# Power.net
KiCad netlist of a schematic drawn in Altium Designer
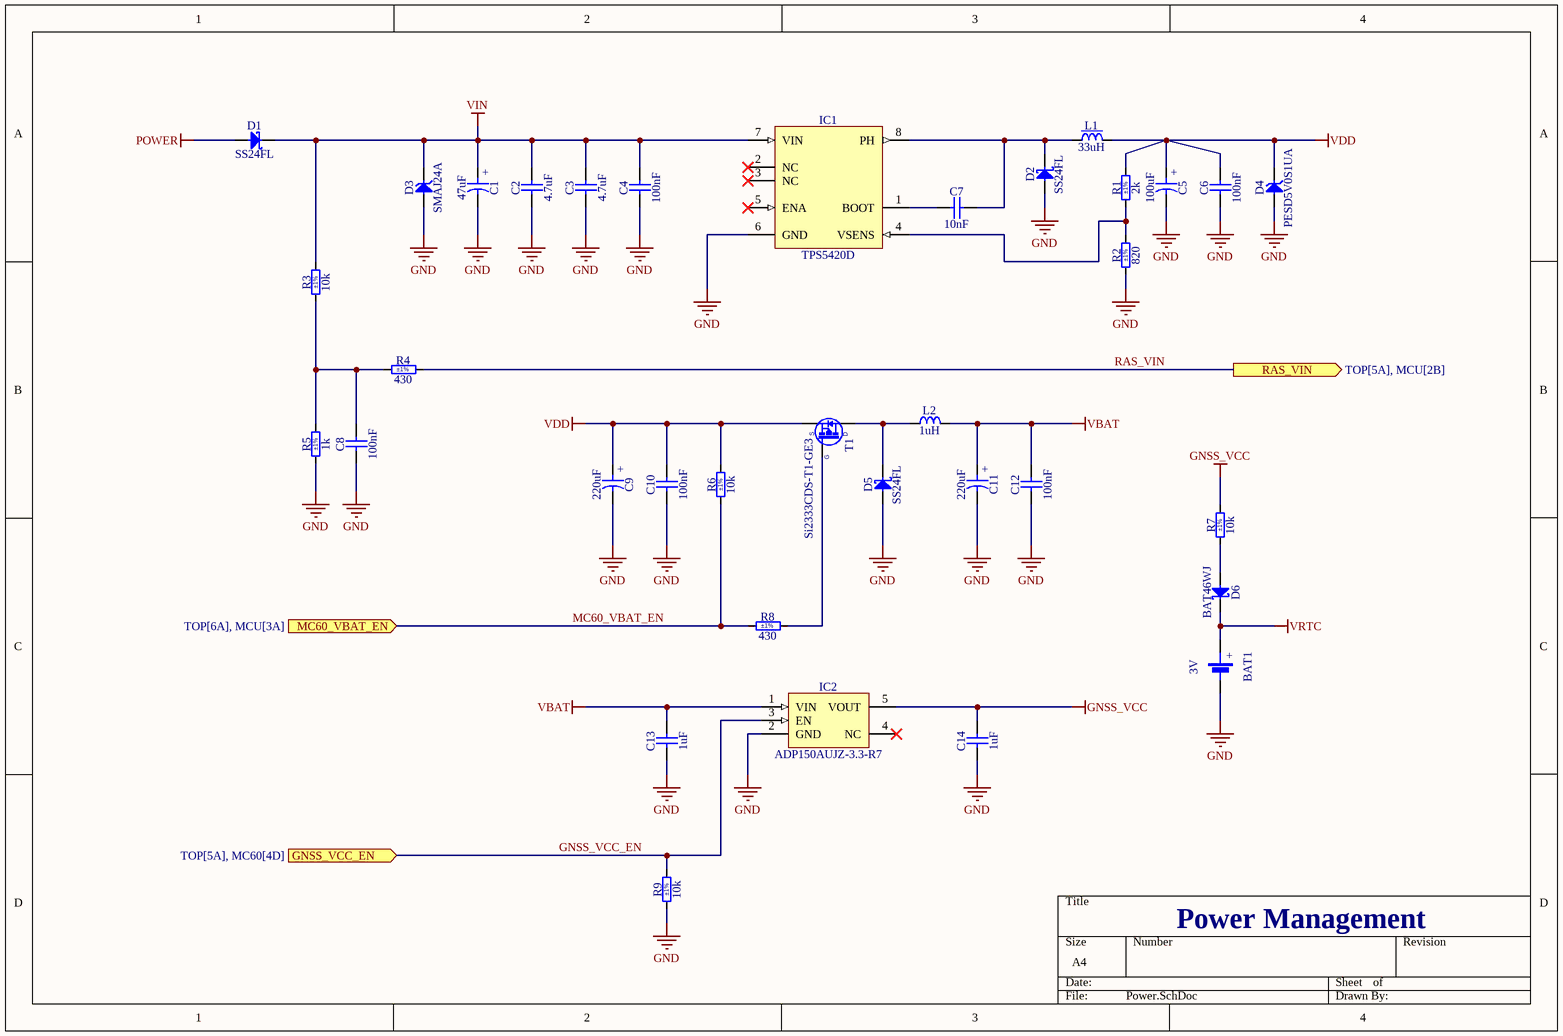
[diagram p0: Power.SchDoc]

(export (version "E")
  (design (tool "Eeschema 10.0.6"))
  (components
    (comp (ref "BAT1")
      (value "3V")
      (footprint "BAT_SEIKO_ML414H_IV01E")
      (description "Battery 2 Pin")
      (fields
        (field (name "PART NUMBER") "BAT_SEIKO_ML414H_IV01E")
        (field (name "POWER") "1mAh")
        (field (name "AUTHOR") "Xusniyor")
      )
      (libsource (lib "Eletro-mechanical") (part "Battery 2 Pin"))
    )
    (comp (ref "C1")
      (value "47uF")
      (footprint "CAPAE660X540N")
      (description "Polarised capacitor")
      (fields
        (field (name "PART NUMBER") "CAE660-540_47UF_35V_20%")
        (field (name "VOLTAGE") "35V")
        (field (name "AUTHOR") "CERN DEM JLC")
      )
      (libsource (lib "Capacitors") (part "Capacitor - polarized"))
    )
    (comp (ref "C2")
      (value "4.7uF")
      (footprint "CAPC5750X200N")
      (description "Non-polarised capacitor")
      (fields
        (field (name "PART NUMBER") "CC2220_4.7UF_100V_10%_X7R")
        (field (name "VOLTAGE") "100V")
        (field (name "AUTHOR") "CERN DEM JLC")
      )
      (libsource (lib "Capacitors") (part "Capacitor - non polarized"))
    )
    (comp (ref "C3")
      (value "4.7uF")
      (footprint "CAPC5750X200N")
      (description "Non-polarised capacitor")
      (fields
        (field (name "PART NUMBER") "CC2220_4.7UF_100V_10%_X7R")
        (field (name "VOLTAGE") "100V")
        (field (name "AUTHOR") "CERN DEM JLC")
      )
      (libsource (lib "Capacitors") (part "Capacitor - non polarized"))
    )
    (comp (ref "C4")
      (value "100nF")
      (footprint "CAPC1608X90N")
      (description "Non-polarised capacitor")
      (fields
        (field (name "PART NUMBER") "CC0603_100NF_100V_10%_X7R")
        (field (name "VOLTAGE") "100V")
        (field (name "AUTHOR") "CERN DEM JLC")
      )
      (libsource (lib "Capacitors") (part "Capacitor - non polarized"))
    )
    (comp (ref "C5")
      (value "100uF")
      (footprint "CAPMP7343X310N")
      (description "Polarised capacitor")
      (fields
        (field (name "PART NUMBER") "CTE7343-31_100UF_10V_10%_LESR0050")
        (field (name "VOLTAGE") "10V")
        (field (name "AUTHOR") "CERN DEM JLC")
      )
      (libsource (lib "Capacitors") (part "Capacitor - polarized"))
    )
    (comp (ref "C6")
      (value "100nF")
      (footprint "CAPC1608X87N")
      (description "Non-polarised capacitor")
      (fields
        (field (name "PART NUMBER") "CC0603_100NF_50V_10%_X7R")
        (field (name "VOLTAGE") "50V")
        (field (name "AUTHOR") "CERN DEM JLC")
      )
      (libsource (lib "Capacitors") (part "Capacitor - non polarized"))
    )
    (comp (ref "C7")
      (value "10nF")
      (footprint "CAPC1608X87N")
      (description "Non-polarised capacitor")
      (fields
        (field (name "PART NUMBER") "CC0603_10NF_50V_10%_X7R")
        (field (name "VOLTAGE") "50V")
        (field (name "AUTHOR") "CERN DEM JLC")
      )
      (libsource (lib "Capacitors") (part "Capacitor - non polarized"))
    )
    (comp (ref "C8")
      (value "100nF")
      (footprint "CAPC1608X87N")
      (description "Non-polarised capacitor")
      (fields
        (field (name "PART NUMBER") "CC0603_100NF_50V_10%_X7R")
        (field (name "VOLTAGE") "50V")
        (field (name "AUTHOR") "CERN DEM JLC")
      )
      (libsource (lib "Capacitors") (part "Capacitor - non polarized"))
    )
    (comp (ref "C9")
      (value "220uF")
      (footprint "CAPAE830X620N")
      (description "Polarised capacitor")
      (fields
        (field (name "PART NUMBER") "CAE830-620_220UF_10V_20%")
        (field (name "VOLTAGE") "10V")
        (field (name "AUTHOR") "CERN DEM JLC")
      )
      (libsource (lib "Capacitors") (part "Capacitor - polarized"))
    )
    (comp (ref "C10")
      (value "100nF")
      (footprint "CAPC1608X87N")
      (description "Non-polarised capacitor")
      (fields
        (field (name "PART NUMBER") "CC0603_100NF_50V_10%_X7R")
        (field (name "VOLTAGE") "50V")
        (field (name "AUTHOR") "CERN DEM JLC")
      )
      (libsource (lib "Capacitors") (part "Capacitor - non polarized"))
    )
    (comp (ref "C11")
      (value "220uF")
      (footprint "CAPAE830X620N")
      (description "Polarised capacitor")
      (fields
        (field (name "PART NUMBER") "CAE830-620_220UF_10V_20%")
        (field (name "VOLTAGE") "10V")
        (field (name "AUTHOR") "CERN DEM JLC")
      )
      (libsource (lib "Capacitors") (part "Capacitor - polarized"))
    )
    (comp (ref "C12")
      (value "100nF")
      (footprint "CAPC1608X87N")
      (description "Non-polarised capacitor")
      (fields
        (field (name "PART NUMBER") "CC0603_100NF_50V_10%_X7R")
        (field (name "VOLTAGE") "50V")
        (field (name "AUTHOR") "CERN DEM JLC")
      )
      (libsource (lib "Capacitors") (part "Capacitor - non polarized"))
    )
    (comp (ref "C13")
      (value "1uF")
      (footprint "CAPC1608X90N")
      (description "Non-polarised capacitor")
      (fields
        (field (name "PART NUMBER") "CC0603_1UF_50V_10%_X7R")
        (field (name "VOLTAGE") "50V")
        (field (name "AUTHOR") "CERN DEM BC")
      )
      (libsource (lib "Capacitors") (part "Capacitor - non polarized"))
    )
    (comp (ref "C14")
      (value "1uF")
      (footprint "CAPC1608X90N")
      (description "Non-polarised capacitor")
      (fields
        (field (name "PART NUMBER") "CC0603_1UF_50V_10%_X7R")
        (field (name "VOLTAGE") "50V")
        (field (name "AUTHOR") "CERN DEM BC")
      )
      (libsource (lib "Capacitors") (part "Capacitor - non polarized"))
    )
    (comp (ref "D1")
      (value "SS24FL")
      (footprint "SODFL3617X108N")
      (description "Schottky Diode")
      (fields
        (field (name "VOLTAGE") "40V")
        (field (name "POWER") "2A")
        (field (name "AUTHOR") "CERN DEM BC")
      )
      (libsource (lib "ICs And Semiconductors") (part "Diode Schottky"))
    )
    (comp (ref "D2")
      (value "SS24FL")
      (footprint "SODFL3617X108N")
      (description "Schottky Diode")
      (fields
        (field (name "VOLTAGE") "40V")
        (field (name "POWER") "2A")
        (field (name "AUTHOR") "CERN DEM BC")
      )
      (libsource (lib "ICs And Semiconductors") (part "Diode Schottky"))
    )
    (comp (ref "D3")
      (value "SMAJ24A")
      (footprint "DIOM5226X262N")
      (description "Transient Voltage Suppressor Diode (Uni-Directional)")
      (fields
        (field (name "VOLTAGE") "24V")
        (field (name "POWER") "400W")
        (field (name "AUTHOR") "CERN DEM JLC")
      )
      (libsource (lib "ICs And Semiconductors") (part "Diode TVS Uni-Directional"))
    )
    (comp (ref "D4")
      (value "PESD5V0S1UA")
      (footprint "SOD2512X110N")
      (description "Transient Voltage Suppressor Diode (Uni-Directional)")
      (fields
        (field (name "VOLTAGE") "5V")
        (field (name "POWER") "890W")
        (field (name "AUTHOR") "CERN DEM JLC")
      )
      (libsource (lib "ICs And Semiconductors") (part "Diode TVS Uni-Directional"))
    )
    (comp (ref "D5")
      (value "SS24FL")
      (footprint "SODFL3617X108N")
      (description "Schottky Diode")
      (fields
        (field (name "VOLTAGE") "40V")
        (field (name "POWER") "2A")
        (field (name "AUTHOR") "CERN DEM BC")
      )
      (libsource (lib "ICs And Semiconductors") (part "Diode Schottky"))
    )
    (comp (ref "D6")
      (value "BAT46WJ")
      (footprint "SODFL2513X80N")
      (description "Schottky Diode")
      (fields
        (field (name "VOLTAGE") "100V")
        (field (name "POWER") "250mA")
        (field (name "AUTHOR") "CERN DEM JLC")
      )
      (libsource (lib "ICs And Semiconductors") (part "Diode Schottky"))
    )
    (comp (ref "IC1")
      (value "TPS5420D")
      (footprint "SOIC127P600X175-8N")
      (description "2A, Wide Input Range, Step-Down SWIFT Converter")
      (fields (field (name "MANUFACTURER") "TEXAS INSTRUMENTS") (field (name "AUTHOR") "CERN DEM JLC"))
      (libsource (lib "ICs And Semiconductors") (part "TPS5420"))
    )
    (comp (ref "IC2")
      (value "ADP150AUJZ-3.3-R7")
      (footprint "SOT95P280X90-5N")
      (description "Ultralow Noise, 150 mA CMOS Linear Regulator")
      (fields (field (name "MANUFACTURER") "ANALOG DEVICES") (field (name "AUTHOR") "CERN DEM JLC"))
      (libsource (lib "ICs And Semiconductors") (part "ADP150AUJZ"))
    )
    (comp (ref "L1")
      (value "33uH")
      (footprint "INDM7066X300N")
      (description "Inductor With Core")
      (fields
        (field (name "PART NUMBER") "IND_33UH_20%_FXL0630-330-M")
        (field (name "POWER") "2A")
        (field (name "AUTHOR") "Xusniyor")
      )
      (libsource (lib "Inductors & Transformers") (part "Inductor With Magnetic core"))
    )
    (comp (ref "L2")
      (value "1uH")
      (footprint "INDC2520X120N")
      (description "Inductor")
      (fields
        (field (name "PART NUMBER") "IND1008_1UH_20%_MURATA_DFE252012P-1R0M=P2")
        (field (name "POWER") "4.3A")
        (field (name "AUTHOR") "Xusniyor")
      )
      (libsource (lib "Inductors & Transformers") (part "Inductor"))
    )
    (comp (ref "R1")
      (value "2k")
      (footprint "RESC1608X55N")
      (description "Resistor - 1%")
      (fields
        (field (name "TOLERANCE") "±1%")
        (field (name "PART NUMBER") "R0603_2K_1%_0.1W_100PPM")
        (field (name "POWER") "0.1W")
        (field (name "AUTHOR") "CERN DEM JLC")
      )
      (libsource (lib "Resistors") (part "Resistor - 1%"))
    )
    (comp (ref "R2")
      (value "820")
      (footprint "RESC1608X55N")
      (description "Resistor - 1%")
      (fields
        (field (name "TOLERANCE") "±1%")
        (field (name "PART NUMBER") "R0603_820R_1%_0.1W_100PPM")
        (field (name "POWER") "0.1W")
        (field (name "AUTHOR") "CERN DEM JLC")
      )
      (libsource (lib "Resistors") (part "Resistor - 1%"))
    )
    (comp (ref "R3")
      (value "10k")
      (footprint "RESC3216X65N")
      (description "Resistor - 1%")
      (fields
        (field (name "TOLERANCE") "±1%")
        (field (name "PART NUMBER") "R1206_10K_1%_0.25W_100PPM")
        (field (name "POWER") "0.25W")
        (field (name "AUTHOR") "CERN DEM JLC")
      )
      (libsource (lib "Resistors") (part "Resistor - 1%"))
    )
    (comp (ref "R4")
      (value "430")
      (footprint "RESC1608X55N")
      (description "Resistor - 1%")
      (fields
        (field (name "TOLERANCE") "±1%")
        (field (name "PART NUMBER") "R0603_430R_1%_0.1W_100PPM")
        (field (name "POWER") "0.1W")
        (field (name "AUTHOR") "CERN DEM JLC")
      )
      (libsource (lib "Resistors") (part "Resistor - 1%"))
    )
    (comp (ref "R5")
      (value "1k")
      (footprint "RESC1608X55N")
      (description "Resistor - 1%")
      (fields
        (field (name "TOLERANCE") "±1%")
        (field (name "PART NUMBER") "R0603_1K_1%_0.1W_100PPM")
        (field (name "POWER") "0.1W")
        (field (name "AUTHOR") "CERN DEM JLC")
      )
      (libsource (lib "Resistors") (part "Resistor - 1%"))
    )
    (comp (ref "R6")
      (value "10k")
      (footprint "RESC1608X55N")
      (description "Resistor - 1%")
      (fields
        (field (name "TOLERANCE") "±1%")
        (field (name "PART NUMBER") "R0603_10K_1%_0.1W_100PPM")
        (field (name "POWER") "0.1W")
        (field (name "AUTHOR") "CERN DEM JLC")
      )
      (libsource (lib "Resistors") (part "Resistor - 1%"))
    )
    (comp (ref "R7")
      (value "10k")
      (footprint "RESC1608X55N")
      (description "Resistor - 1%")
      (fields
        (field (name "TOLERANCE") "±1%")
        (field (name "PART NUMBER") "R0603_10K_1%_0.1W_100PPM")
        (field (name "POWER") "0.1W")
        (field (name "AUTHOR") "CERN DEM JLC")
      )
      (libsource (lib "Resistors") (part "Resistor - 1%"))
    )
    (comp (ref "R8")
      (value "430")
      (footprint "RESC1608X55N")
      (description "Resistor - 1%")
      (fields
        (field (name "TOLERANCE") "±1%")
        (field (name "PART NUMBER") "R0603_430R_1%_0.1W_100PPM")
        (field (name "POWER") "0.1W")
        (field (name "AUTHOR") "CERN DEM JLC")
      )
      (libsource (lib "Resistors") (part "Resistor - 1%"))
    )
    (comp (ref "R9")
      (value "10k")
      (footprint "RESC1608X55N")
      (description "Resistor - 1%")
      (fields
        (field (name "TOLERANCE") "±1%")
        (field (name "PART NUMBER") "R0603_10K_1%_0.1W_100PPM")
        (field (name "POWER") "0.1W")
        (field (name "AUTHOR") "CERN DEM JLC")
      )
      (libsource (lib "Resistors") (part "Resistor - 1%"))
    )
    (comp (ref "T1")
      (value "Si2333CDS-T1-GE3")
      (footprint "SOT95P237X112-3N")
      (description "P-CHANNEL MOSFET WITH DIODE")
      (fields (field (name "MANUFACTURER") "VISHAY SILICONIX") (field (name "AUTHOR") "CERN DEM JLC"))
      (libsource (lib "ICs And Semiconductors") (part "P-MOSFET-D 1G 2S 3D"))
    )
  )
  (nets
    (net (code "1") (name "/GNSS_VCC_EN") (class "Default")
      (node (ref "IC2") (pin "3") (pinfunction "EN_3") (pintype "input"))
      (node (ref "R9") (pin "2") (pinfunction "2_2") (pintype "passive"))
    )
    (net (code "2") (name "/MC60_VBAT_EN") (class "Default")
      (node (ref "R6") (pin "1") (pinfunction "1_1") (pintype "passive"))
      (node (ref "R8") (pin "1") (pinfunction "1_1") (pintype "passive"))
    )
    (net (code "3") (name "/RAS_VIN") (class "Default")
      (node (ref "R4") (pin "2") (pinfunction "2_2") (pintype "passive"))
    )
    (net (code "4") (name "GND") (class "Default")
      (node (ref "BAT1") (pin "2") (pinfunction "MINUS_2") (pintype "power_in"))
      (node (ref "C1") (pin "2") (pinfunction "2_2") (pintype "passive"))
      (node (ref "C10") (pin "1") (pinfunction "1_1") (pintype "passive"))
      (node (ref "C11") (pin "2") (pinfunction "2_2") (pintype "passive"))
      (node (ref "C12") (pin "1") (pinfunction "1_1") (pintype "passive"))
      (node (ref "C13") (pin "1") (pinfunction "1_1") (pintype "passive"))
      (node (ref "C14") (pin "1") (pinfunction "1_1") (pintype "passive"))
      (node (ref "C2") (pin "1") (pinfunction "1_1") (pintype "passive"))
      (node (ref "C3") (pin "1") (pinfunction "1_1") (pintype "passive"))
      (node (ref "C4") (pin "1") (pinfunction "1_1") (pintype "passive"))
      (node (ref "C5") (pin "2") (pinfunction "2_2") (pintype "passive"))
      (node (ref "C6") (pin "1") (pinfunction "1_1") (pintype "passive"))
      (node (ref "C8") (pin "1") (pinfunction "1_1") (pintype "passive"))
      (node (ref "C9") (pin "2") (pinfunction "2_2") (pintype "passive"))
      (node (ref "D2") (pin "2") (pinfunction "A_2") (pintype "passive"))
      (node (ref "D3") (pin "2") (pinfunction "A_2") (pintype "passive"))
      (node (ref "D4") (pin "2") (pinfunction "A_2") (pintype "passive"))
      (node (ref "D5") (pin "2") (pinfunction "A_2") (pintype "passive"))
      (node (ref "IC1") (pin "6") (pinfunction "GND_6") (pintype "power_in"))
      (node (ref "IC2") (pin "2") (pinfunction "GND_2") (pintype "power_in"))
      (node (ref "R2") (pin "1") (pinfunction "1_1") (pintype "passive"))
      (node (ref "R5") (pin "1") (pinfunction "1_1") (pintype "passive"))
      (node (ref "R9") (pin "1") (pinfunction "1_1") (pintype "passive"))
    )
    (net (code "5") (name "GNSS_VCC") (class "Default")
      (node (ref "C14") (pin "2") (pinfunction "2_2") (pintype "passive"))
      (node (ref "IC2") (pin "5") (pinfunction "VOUT_5") (pintype "power_in"))
      (node (ref "R7") (pin "2") (pinfunction "2_2") (pintype "passive"))
    )
    (net (code "6") (name "Net-(C8-Pad2)") (class "Default")
      (node (ref "C8") (pin "2") (pinfunction "2_2") (pintype "passive"))
      (node (ref "R3") (pin "1") (pinfunction "1_1") (pintype "passive"))
      (node (ref "R4") (pin "1") (pinfunction "1_1") (pintype "passive"))
      (node (ref "R5") (pin "2") (pinfunction "2_2") (pintype "passive"))
    )
    (net (code "7") (name "Net-(D2-C)") (class "Default")
      (node (ref "C7") (pin "2") (pinfunction "2_2") (pintype "passive"))
      (node (ref "D2") (pin "1") (pinfunction "C_1") (pintype "passive"))
      (node (ref "IC1") (pin "8") (pinfunction "PH_8") (pintype "output"))
      (node (ref "L1") (pin "1") (pinfunction "1_1") (pintype "passive"))
    )
    (net (code "8") (name "Net-(D5-C)") (class "Default")
      (node (ref "D5") (pin "1") (pinfunction "C_1") (pintype "passive"))
      (node (ref "L2") (pin "1") (pinfunction "1_1") (pintype "passive"))
      (node (ref "T1") (pin "3") (pinfunction "D_3") (pintype "passive"))
    )
    (net (code "9") (name "Net-(D6-A)") (class "Default")
      (node (ref "D6") (pin "2") (pinfunction "A_2") (pintype "passive"))
      (node (ref "R7") (pin "1") (pinfunction "1_1") (pintype "passive"))
    )
    (net (code "10") (name "Net-(IC1-BOOT)") (class "Default")
      (node (ref "C7") (pin "1") (pinfunction "1_1") (pintype "passive"))
      (node (ref "IC1") (pin "1") (pinfunction "BOOT_1") (pintype "passive"))
    )
    (net (code "11") (name "Net-(IC1-VSENS)") (class "Default")
      (node (ref "IC1") (pin "4") (pinfunction "VSENS_4") (pintype "input"))
      (node (ref "R1") (pin "1") (pinfunction "1_1") (pintype "passive"))
      (node (ref "R2") (pin "2") (pinfunction "2_2") (pintype "passive"))
    )
    (net (code "12") (name "Net-(T1-G)") (class "Default")
      (node (ref "R8") (pin "2") (pinfunction "2_2") (pintype "passive"))
      (node (ref "T1") (pin "1") (pinfunction "G_1") (pintype "passive"))
    )
    (net (code "13") (name "POWER") (class "Default")
      (node (ref "D1") (pin "2") (pinfunction "A_2") (pintype "passive"))
    )
    (net (code "14") (name "VBAT") (class "Default")
      (node (ref "C11") (pin "1") (pinfunction "1_1") (pintype "passive"))
      (node (ref "C12") (pin "2") (pinfunction "2_2") (pintype "passive"))
      (node (ref "C13") (pin "2") (pinfunction "2_2") (pintype "passive"))
      (node (ref "IC2") (pin "1") (pinfunction "VIN_1") (pintype "input"))
      (node (ref "L2") (pin "2") (pinfunction "2_2") (pintype "passive"))
    )
    (net (code "15") (name "VDD") (class "Default")
      (node (ref "C10") (pin "2") (pinfunction "2_2") (pintype "passive"))
      (node (ref "C5") (pin "1") (pinfunction "1_1") (pintype "passive"))
      (node (ref "C6") (pin "2") (pinfunction "2_2") (pintype "passive"))
      (node (ref "C9") (pin "1") (pinfunction "1_1") (pintype "passive"))
      (node (ref "D4") (pin "1") (pinfunction "C_1") (pintype "passive"))
      (node (ref "L1") (pin "2") (pinfunction "2_2") (pintype "passive"))
      (node (ref "R1") (pin "2") (pinfunction "2_2") (pintype "passive"))
      (node (ref "R6") (pin "2") (pinfunction "2_2") (pintype "passive"))
      (node (ref "T1") (pin "2") (pinfunction "S_2") (pintype "passive"))
    )
    (net (code "16") (name "VIN") (class "Default")
      (node (ref "C1") (pin "1") (pinfunction "1_1") (pintype "passive"))
      (node (ref "C2") (pin "2") (pinfunction "2_2") (pintype "passive"))
      (node (ref "C3") (pin "2") (pinfunction "2_2") (pintype "passive"))
      (node (ref "C4") (pin "2") (pinfunction "2_2") (pintype "passive"))
      (node (ref "D1") (pin "1") (pinfunction "C_1") (pintype "passive"))
      (node (ref "D3") (pin "1") (pinfunction "C_1") (pintype "passive"))
      (node (ref "IC1") (pin "7") (pinfunction "VIN_7") (pintype "input"))
      (node (ref "R3") (pin "2") (pinfunction "2_2") (pintype "passive"))
    )
    (net (code "17") (name "VRTC") (class "Default")
      (node (ref "BAT1") (pin "1") (pinfunction "PLUS_1") (pintype "power_in"))
      (node (ref "D6") (pin "1") (pinfunction "C_1") (pintype "passive"))
    )
    (net (code "18") (name "unconnected-(IC1-ENA-Pad5)") (class "Default")
      (node (ref "IC1") (pin "5") (pinfunction "ENA_5") (pintype "input+no_connect"))
    )
    (net (code "19") (name "unconnected-(IC1-NC-Pad2)") (class "Default")
      (node (ref "IC1") (pin "2") (pinfunction "NC_2") (pintype "passive+no_connect"))
    )
    (net (code "20") (name "unconnected-(IC1-NC-Pad3)") (class "Default")
      (node (ref "IC1") (pin "3") (pinfunction "NC_3") (pintype "passive+no_connect"))
    )
    (net (code "21") (name "unconnected-(IC2-NC-Pad4)") (class "Default")
      (node (ref "IC2") (pin "4") (pinfunction "NC_4") (pintype "passive+no_connect"))
    )
  )
)
